# untitled.net
KiCad netlist of a schematic drawn in EAGLE
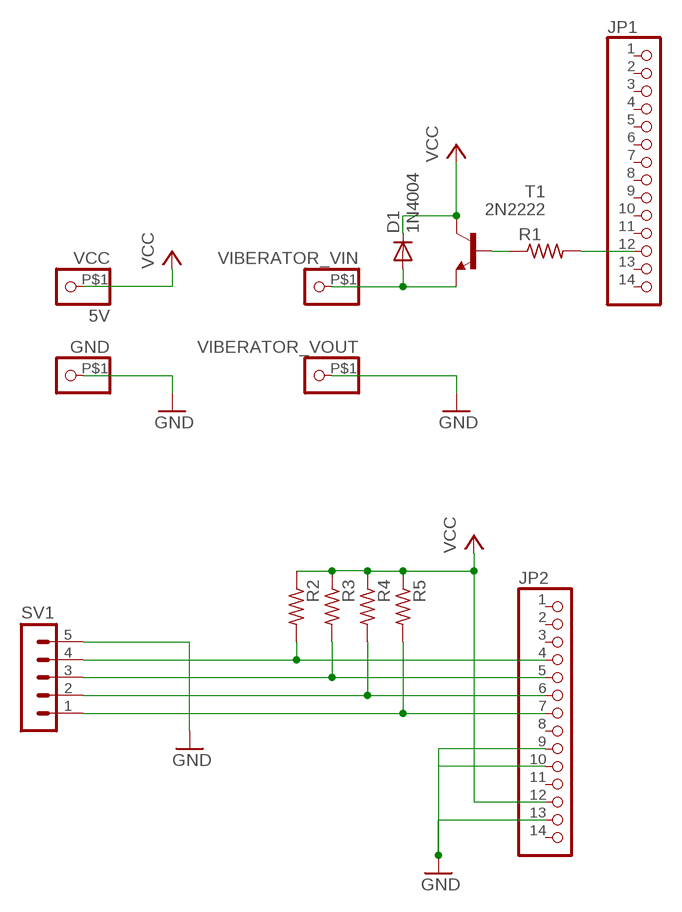
[diagram p0: schematic, sheet 1]

(export (version "E")
  (design (tool "Eeschema 10.0.6"))
  (components
    (comp (ref "D1")
      (value "1N4004")
      (footprint "eagle-import:DO41-10")
      (libsource (lib "eagle-import") (part "1N4004"))
    )
    (comp (ref "GND")
      (value "PINHD-1X1-BIGPOGO")
      (footprint "eagle-import:1X1-BIGPOGO")
      (libsource (lib "eagle-import") (part "PINHD-1X1-BIGPOGO"))
    )
    (comp (ref "JP1")
      (value "PINHD-1X14-CB")
      (footprint "eagle-import:1X14-CB")
      (libsource (lib "eagle-import") (part "PINHD-1X14-CB"))
    )
    (comp (ref "JP2")
      (value "PINHD-1X14-CB")
      (footprint "eagle-import:1X14-CB")
      (libsource (lib "eagle-import") (part "PINHD-1X14-CB"))
    )
    (comp (ref "R1")
      (value "R-US_R0805")
      (footprint "eagle-import:R0805")
      (libsource (lib "eagle-import") (part "R-US_R0805"))
    )
    (comp (ref "R2")
      (value "R-US_R0805")
      (footprint "eagle-import:R0805")
      (libsource (lib "eagle-import") (part "R-US_R0805"))
    )
    (comp (ref "R3")
      (value "R-US_R0805")
      (footprint "eagle-import:R0805")
      (libsource (lib "eagle-import") (part "R-US_R0805"))
    )
    (comp (ref "R4")
      (value "R-US_R0805")
      (footprint "eagle-import:R0805")
      (libsource (lib "eagle-import") (part "R-US_R0805"))
    )
    (comp (ref "R5")
      (value "R-US_R0805")
      (footprint "eagle-import:R0805")
      (libsource (lib "eagle-import") (part "R-US_R0805"))
    )
    (comp (ref "SV1")
      (value "MA05-1")
      (footprint "eagle-import:MA05-1")
      (libsource (lib "eagle-import") (part "MA05-1"))
    )
    (comp (ref "T1")
      (value "2N2222")
      (footprint "eagle-import:TO92-EBC-OVAL")
      (libsource (lib "eagle-import") (part "2N2222"))
    )
    (comp (ref "VCC")
      (value "5V")
      (footprint "eagle-import:1X1-BIGPOGO")
      (libsource (lib "eagle-import") (part "PINHD-1X1-BIGPOGO"))
    )
    (comp (ref "VIBERATOR_VIN")
      (value "PINHD-1X1-BIGPOGO")
      (footprint "eagle-import:1X1-BIGPOGO")
      (libsource (lib "eagle-import") (part "PINHD-1X1-BIGPOGO"))
    )
    (comp (ref "VIBERATOR_VOUT")
      (value "PINHD-1X1-BIGPOGO")
      (footprint "eagle-import:1X1-BIGPOGO")
      (libsource (lib "eagle-import") (part "PINHD-1X1-BIGPOGO"))
    )
  )
  (nets
    (net (code "1") (name "GND") (class "Default")
      (node (ref "GND") (pin "P$1") (pinfunction "1_P$1") (pintype "passive"))
      (node (ref "JP2") (pin "10") (pinfunction "10_10") (pintype "passive"))
      (node (ref "JP2") (pin "13") (pinfunction "13_13") (pintype "passive"))
      (node (ref "JP2") (pin "9") (pinfunction "9_9") (pintype "passive"))
      (node (ref "SV1") (pin "5") (pinfunction "5_5") (pintype "passive"))
      (node (ref "VIBERATOR_VOUT") (pin "P$1") (pinfunction "1_P$1") (pintype "passive"))
    )
    (net (code "2") (name "Net-(JP1-Pad12)") (class "Default")
      (node (ref "JP1") (pin "12") (pinfunction "12_12") (pintype "passive"))
      (node (ref "R1") (pin "2") (pinfunction "2_2") (pintype "passive"))
    )
    (net (code "3") (name "Net-(JP2-Pad4)") (class "Default")
      (node (ref "JP2") (pin "4") (pinfunction "4_4") (pintype "passive"))
      (node (ref "R2") (pin "2") (pinfunction "2_2") (pintype "passive"))
      (node (ref "SV1") (pin "4") (pinfunction "4_4") (pintype "passive"))
    )
    (net (code "4") (name "Net-(JP2-Pad5)") (class "Default")
      (node (ref "JP2") (pin "5") (pinfunction "5_5") (pintype "passive"))
      (node (ref "R3") (pin "2") (pinfunction "2_2") (pintype "passive"))
      (node (ref "SV1") (pin "3") (pinfunction "3_3") (pintype "passive"))
    )
    (net (code "5") (name "Net-(JP2-Pad6)") (class "Default")
      (node (ref "JP2") (pin "6") (pinfunction "6_6") (pintype "passive"))
      (node (ref "R4") (pin "2") (pinfunction "2_2") (pintype "passive"))
      (node (ref "SV1") (pin "2") (pinfunction "2_2") (pintype "passive"))
    )
    (net (code "6") (name "Net-(JP2-Pad7)") (class "Default")
      (node (ref "JP2") (pin "7") (pinfunction "7_7") (pintype "passive"))
      (node (ref "R5") (pin "2") (pinfunction "2_2") (pintype "passive"))
      (node (ref "SV1") (pin "1") (pinfunction "1_1") (pintype "passive"))
    )
    (net (code "7") (name "Net-(R1-Pad1)") (class "Default")
      (node (ref "R1") (pin "1") (pinfunction "1_1") (pintype "passive"))
      (node (ref "T1") (pin "B") (pinfunction "B_B") (pintype "passive"))
    )
    (net (code "8") (name "Net-(VIBERATOR_VIN-1)") (class "Default")
      (node (ref "D1") (pin "A") (pinfunction "A_A") (pintype "passive"))
      (node (ref "T1") (pin "E") (pinfunction "E_E") (pintype "passive"))
      (node (ref "VIBERATOR_VIN") (pin "P$1") (pinfunction "1_P$1") (pintype "passive"))
    )
    (net (code "9") (name "VCC") (class "Default")
      (node (ref "D1") (pin "C") (pinfunction "C_C") (pintype "passive"))
      (node (ref "JP2") (pin "12") (pinfunction "12_12") (pintype "passive"))
      (node (ref "R2") (pin "1") (pinfunction "1_1") (pintype "passive"))
      (node (ref "R3") (pin "1") (pinfunction "1_1") (pintype "passive"))
      (node (ref "R4") (pin "1") (pinfunction "1_1") (pintype "passive"))
      (node (ref "R5") (pin "1") (pinfunction "1_1") (pintype "passive"))
      (node (ref "T1") (pin "C") (pinfunction "C_C") (pintype "passive"))
      (node (ref "VCC") (pin "P$1") (pinfunction "1_P$1") (pintype "passive"))
    )
    (net (code "10") (name "unconnected-(JP1-Pad1)") (class "Default")
      (node (ref "JP1") (pin "1") (pinfunction "1_1") (pintype "passive"))
    )
    (net (code "11") (name "unconnected-(JP1-Pad2)") (class "Default")
      (node (ref "JP1") (pin "2") (pinfunction "2_2") (pintype "passive"))
    )
    (net (code "12") (name "unconnected-(JP1-Pad3)") (class "Default")
      (node (ref "JP1") (pin "3") (pinfunction "3_3") (pintype "passive"))
    )
    (net (code "13") (name "unconnected-(JP1-Pad4)") (class "Default")
      (node (ref "JP1") (pin "4") (pinfunction "4_4") (pintype "passive"))
    )
    (net (code "14") (name "unconnected-(JP1-Pad5)") (class "Default")
      (node (ref "JP1") (pin "5") (pinfunction "5_5") (pintype "passive"))
    )
    (net (code "15") (name "unconnected-(JP1-Pad6)") (class "Default")
      (node (ref "JP1") (pin "6") (pinfunction "6_6") (pintype "passive"))
    )
    (net (code "16") (name "unconnected-(JP1-Pad7)") (class "Default")
      (node (ref "JP1") (pin "7") (pinfunction "7_7") (pintype "passive"))
    )
    (net (code "17") (name "unconnected-(JP1-Pad8)") (class "Default")
      (node (ref "JP1") (pin "8") (pinfunction "8_8") (pintype "passive"))
    )
    (net (code "18") (name "unconnected-(JP1-Pad9)") (class "Default")
      (node (ref "JP1") (pin "9") (pinfunction "9_9") (pintype "passive"))
    )
    (net (code "19") (name "unconnected-(JP1-Pad10)") (class "Default")
      (node (ref "JP1") (pin "10") (pinfunction "10_10") (pintype "passive"))
    )
    (net (code "20") (name "unconnected-(JP1-Pad11)") (class "Default")
      (node (ref "JP1") (pin "11") (pinfunction "11_11") (pintype "passive"))
    )
    (net (code "21") (name "unconnected-(JP1-Pad13)") (class "Default")
      (node (ref "JP1") (pin "13") (pinfunction "13_13") (pintype "passive"))
    )
    (net (code "22") (name "unconnected-(JP1-Pad14)") (class "Default")
      (node (ref "JP1") (pin "14") (pinfunction "14_14") (pintype "passive"))
    )
    (net (code "23") (name "unconnected-(JP2-Pad1)") (class "Default")
      (node (ref "JP2") (pin "1") (pinfunction "1_1") (pintype "passive"))
    )
    (net (code "24") (name "unconnected-(JP2-Pad2)") (class "Default")
      (node (ref "JP2") (pin "2") (pinfunction "2_2") (pintype "passive"))
    )
    (net (code "25") (name "unconnected-(JP2-Pad3)") (class "Default")
      (node (ref "JP2") (pin "3") (pinfunction "3_3") (pintype "passive"))
    )
    (net (code "26") (name "unconnected-(JP2-Pad8)") (class "Default")
      (node (ref "JP2") (pin "8") (pinfunction "8_8") (pintype "passive"))
    )
    (net (code "27") (name "unconnected-(JP2-Pad11)") (class "Default")
      (node (ref "JP2") (pin "11") (pinfunction "11_11") (pintype "passive"))
    )
    (net (code "28") (name "unconnected-(JP2-Pad14)") (class "Default")
      (node (ref "JP2") (pin "14") (pinfunction "14_14") (pintype "passive"))
    )
  )
)
